# GSM_SIM.net
KiCad netlist of a schematic drawn in Altium Designer
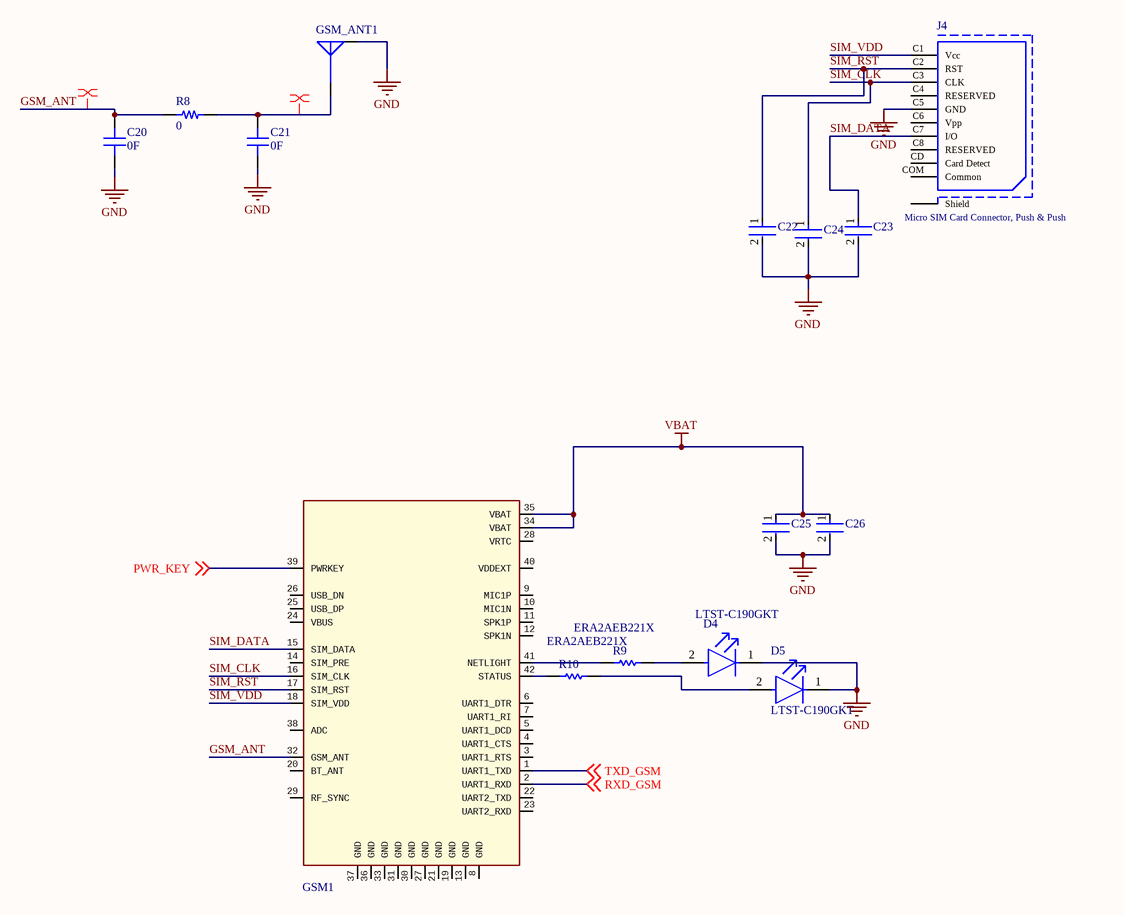
[diagram p0: GSM & SIM.SchDoc]

(export (version "E")
  (design (tool "Eeschema 10.0.6"))
  (components
    (comp (ref "C20")
      (value "0F")
      (footprint "CAP 0402_1005")
      (description "SMT Capacitor")
      (libsource (lib "Capacitor") (part "Cap 0402"))
    )
    (comp (ref "C21")
      (value "0F")
      (footprint "CAP 0402_1005")
      (description "SMT Capacitor")
      (libsource (lib "Capacitor") (part "Cap 0402"))
    )
    (comp (ref "C22")
      (value "04023A330JAT2A")
      (footprint "FP-0402-L_1_0_1-W_0_5_0_1-IPC_A")
      (description "General Purpose Ceramic Capacitor, 0402, 33pF, 5%, C0G, 30ppm/°C, 25V")
      (fields (field (name "TOLERANCE") "5%"))
      (libsource (lib "Altium Content Vault") (part "b4654b650e69147ec39a6b967a45e02"))
    )
    (comp (ref "C23")
      (value "04023A330JAT2A")
      (footprint "FP-0402-L_1_0_1-W_0_5_0_1-IPC_A")
      (description "General Purpose Ceramic Capacitor, 0402, 33pF, 5%, C0G, 30ppm/°C, 25V")
      (fields (field (name "TOLERANCE") "5%"))
      (libsource (lib "Altium Content Vault") (part "b4654b650e69147ec39a6b967a45e02"))
    )
    (comp (ref "C24")
      (value "04023A330JAT2A")
      (footprint "FP-0402-L_1_0_1-W_0_5_0_1-IPC_A")
      (description "General Purpose Ceramic Capacitor, 0402, 33pF, 5%, C0G, 30ppm/°C, 25V")
      (fields (field (name "TOLERANCE") "5%"))
      (libsource (lib "Altium Content Vault") (part "b4654b650e69147ec39a6b967a45e02"))
    )
    (comp (ref "C25")
      (value "04025A330JAT2A")
      (footprint "FP-0402-L_1_0_1-W_0_5_0_1-IPC_A")
      (description "General Purpose Ceramic Capacitor, 0402, 33pF, 5%, C0G, 30ppm/°C, 50V")
      (fields (field (name "TOLERANCE") "5%") (field (name "VOLTAGE") "50V"))
      (libsource (lib "Altium Content Vault") (part "b4654b650e69147ec39a6b967a45e02"))
    )
    (comp (ref "C26")
      (value "C1005C0G1H100D050BA")
      (footprint "FP-C1005-050-0_05-IPC_C")
      (description "CAP CER 10PF 50V C0G 0402")
      (fields (field (name "VOLTAGE") "50V"))
      (libsource (lib "Altium Content Vault") (part "b4654b650e69147ec39a6b967a45e02"))
    )
    (comp (ref "D4")
      (value "LTST-C190GKT")
      (footprint "FP-LTST-C190GKT-MFG")
      (description "LED GREEN CLEAR CHIP SMD")
      (fields (field (name "VOLTAGE") "2V"))
      (libsource (lib "Altium Content Vault") (part "8706943c75ba83719d021d2fdc84c58"))
    )
    (comp (ref "D5")
      (value "LTST-C190GKT")
      (footprint "FP-LTST-C190GKT-MFG")
      (description "LED GREEN CLEAR CHIP SMD")
      (fields (field (name "VOLTAGE") "2V"))
      (libsource (lib "Altium Content Vault") (part "8706943c75ba83719d021d2fdc84c58"))
    )
    (comp (ref "GSM1")
      (value "SIM800C")
      (footprint "Sim800C")
      (libsource (lib "GSM Shutter lock system") (part "SIM800C"))
    )
    (comp (ref "GSM_ANT1")
      (value "UFL")
      (footprint "MOLEX SD-734120110")
      (fields (field (name "PARTNUMBER") "MOLEX SD-734120110"))
      (libsource (lib "Conn RF") (part "UFL MOLEX SD-734120110"))
    )
    (comp (ref "J4")
      (value "Micro SIM Card Connector, Push & Push")
      (footprint "693021010811")
      (description "WR-CRD Micro SIM Card Connector, Push & Push, with Card Detection")
      (fields (field (name "PARTNUMBER") "693021010811") (field (name "PUBLISHER") "Wurth Elektronik"))
      (libsource (lib "Conn Card") (part "Micro SIM Card 693021010811"))
    )
    (comp (ref "R8")
      (value "0")
      (footprint "RES 0402_1005")
      (description "SMT Resistor")
      (libsource (lib "Resistor") (part "Res 0402"))
    )
    (comp (ref "R9")
      (value "ERA2AEB221X")
      (footprint "RESC1005X40X25LL10T10")
      (fields (field (name "MANUFACTURER") "Panasonic"))
      (libsource (lib "Altium Content Vault") (part "RES"))
    )
    (comp (ref "R10")
      (value "ERA2AEB221X")
      (footprint "RESC1005X40X25LL10T10")
      (fields (field (name "MANUFACTURER") "Panasonic"))
      (libsource (lib "Altium Content Vault") (part "RES"))
    )
  )
  (nets
    (net (code "1") (name "/GSM_ANT") (class "Default")
      (node (ref "C20") (pin "2") (pinfunction "2_2") (pintype "passive"))
      (node (ref "GSM1") (pin "32") (pinfunction "GSM_ANT_32") (pintype "passive"))
      (node (ref "R8") (pin "1") (pinfunction "1_1") (pintype "passive"))
    )
    (net (code "2") (name "/SIM_CLK") (class "Default")
      (node (ref "C24") (pin "1") (pinfunction "1_1") (pintype "passive"))
      (node (ref "GSM1") (pin "16") (pinfunction "SIM_CLK_16") (pintype "passive"))
      (node (ref "J4") (pin "C3") (pinfunction "CLK_C3") (pintype "passive"))
    )
    (net (code "3") (name "/SIM_DATA") (class "Default")
      (node (ref "C23") (pin "1") (pinfunction "1_1") (pintype "passive"))
      (node (ref "GSM1") (pin "15") (pinfunction "SIM_DATA_15") (pintype "passive"))
      (node (ref "J4") (pin "C7") (pinfunction "I/O_C7") (pintype "passive"))
    )
    (net (code "4") (name "/SIM_RST") (class "Default")
      (node (ref "C22") (pin "1") (pinfunction "1_1") (pintype "passive"))
      (node (ref "GSM1") (pin "17") (pinfunction "SIM_RST_17") (pintype "passive"))
      (node (ref "J4") (pin "C2") (pinfunction "RST_C2") (pintype "passive"))
    )
    (net (code "5") (name "/SIM_VDD") (class "Default")
      (node (ref "GSM1") (pin "18") (pinfunction "SIM_VDD_18") (pintype "passive"))
      (node (ref "J4") (pin "C1") (pinfunction "Vcc_C1") (pintype "passive"))
    )
    (net (code "6") (name "GND") (class "Default")
      (node (ref "C20") (pin "1") (pinfunction "1_1") (pintype "passive"))
      (node (ref "C21") (pin "1") (pinfunction "1_1") (pintype "passive"))
      (node (ref "C22") (pin "2") (pinfunction "2_2") (pintype "passive"))
      (node (ref "C23") (pin "2") (pinfunction "2_2") (pintype "passive"))
      (node (ref "C24") (pin "2") (pinfunction "2_2") (pintype "passive"))
      (node (ref "C25") (pin "2") (pinfunction "2_2") (pintype "passive"))
      (node (ref "C26") (pin "2") (pinfunction "2_2") (pintype "passive"))
      (node (ref "D4") (pin "1") (pinfunction "C_1") (pintype "passive"))
      (node (ref "D5") (pin "1") (pinfunction "C_1") (pintype "passive"))
      (node (ref "GSM_ANT1") (pin "G") (pinfunction "G_G") (pintype "passive"))
      (node (ref "J4") (pin "C5") (pinfunction "GND_C5") (pintype "passive"))
    )
    (net (code "7") (name "Net-(C21-Pad2)") (class "Default")
      (node (ref "C21") (pin "2") (pinfunction "2_2") (pintype "passive"))
      (node (ref "GSM_ANT1") (pin "S") (pinfunction "S_S") (pintype "passive"))
      (node (ref "R8") (pin "2") (pinfunction "2_2") (pintype "passive"))
    )
    (net (code "8") (name "Net-(D4-A)") (class "Default")
      (node (ref "D4") (pin "2") (pinfunction "A_2") (pintype "passive"))
      (node (ref "R9") (pin "2") (pinfunction "2_2") (pintype "passive"))
    )
    (net (code "9") (name "Net-(D5-A)") (class "Default")
      (node (ref "D5") (pin "2") (pinfunction "A_2") (pintype "passive"))
      (node (ref "R10") (pin "2") (pinfunction "2_2") (pintype "passive"))
    )
    (net (code "10") (name "Net-(GSM1-NETLIGHT)") (class "Default")
      (node (ref "GSM1") (pin "41") (pinfunction "NETLIGHT_41") (pintype "passive"))
      (node (ref "R9") (pin "1") (pinfunction "1_1") (pintype "passive"))
    )
    (net (code "11") (name "Net-(GSM1-STATUS)") (class "Default")
      (node (ref "GSM1") (pin "42") (pinfunction "STATUS_42") (pintype "passive"))
      (node (ref "R10") (pin "1") (pinfunction "1_1") (pintype "passive"))
    )
    (net (code "12") (name "PWR_KEY") (class "Default")
      (node (ref "GSM1") (pin "39") (pinfunction "PWRKEY_39") (pintype "passive"))
    )
    (net (code "13") (name "RXD_GSM") (class "Default")
      (node (ref "GSM1") (pin "2") (pinfunction "UART1_RXD_2") (pintype "passive"))
    )
    (net (code "14") (name "TXD_GSM") (class "Default")
      (node (ref "GSM1") (pin "1") (pinfunction "UART1_TXD_1") (pintype "passive"))
    )
    (net (code "15") (name "VBAT") (class "Default")
      (node (ref "C25") (pin "1") (pinfunction "1_1") (pintype "passive"))
      (node (ref "C26") (pin "1") (pinfunction "1_1") (pintype "passive"))
      (node (ref "GSM1") (pin "34") (pinfunction "VBAT_34") (pintype "passive"))
      (node (ref "GSM1") (pin "35") (pinfunction "VBAT_35") (pintype "passive"))
    )
    (net (code "16") (name "unconnected-(GSM1-ADC-Pad38)") (class "Default")
      (node (ref "GSM1") (pin "38") (pinfunction "ADC_38") (pintype "passive"))
    )
    (net (code "17") (name "unconnected-(GSM1-BT_ANT-Pad20)") (class "Default")
      (node (ref "GSM1") (pin "20") (pinfunction "BT_ANT_20") (pintype "passive"))
    )
    (net (code "18") (name "unconnected-(GSM1-GND-Pad8)") (class "Default")
      (node (ref "GSM1") (pin "8") (pinfunction "GND_8") (pintype "passive"))
    )
    (net (code "19") (name "unconnected-(GSM1-GND-Pad13)") (class "Default")
      (node (ref "GSM1") (pin "13") (pinfunction "GND_13") (pintype "passive"))
    )
    (net (code "20") (name "unconnected-(GSM1-GND-Pad19)") (class "Default")
      (node (ref "GSM1") (pin "19") (pinfunction "GND_19") (pintype "passive"))
    )
    (net (code "21") (name "unconnected-(GSM1-GND-Pad21)") (class "Default")
      (node (ref "GSM1") (pin "21") (pinfunction "GND_21") (pintype "passive"))
    )
    (net (code "22") (name "unconnected-(GSM1-GND-Pad27)") (class "Default")
      (node (ref "GSM1") (pin "27") (pinfunction "GND_27") (pintype "passive"))
    )
    (net (code "23") (name "unconnected-(GSM1-GND-Pad30)") (class "Default")
      (node (ref "GSM1") (pin "30") (pinfunction "GND_30") (pintype "passive"))
    )
    (net (code "24") (name "unconnected-(GSM1-GND-Pad31)") (class "Default")
      (node (ref "GSM1") (pin "31") (pinfunction "GND_31") (pintype "passive"))
    )
    (net (code "25") (name "unconnected-(GSM1-GND-Pad33)") (class "Default")
      (node (ref "GSM1") (pin "33") (pinfunction "GND_33") (pintype "passive"))
    )
    (net (code "26") (name "unconnected-(GSM1-GND-Pad36)") (class "Default")
      (node (ref "GSM1") (pin "36") (pinfunction "GND_36") (pintype "passive"))
    )
    (net (code "27") (name "unconnected-(GSM1-GND-Pad37)") (class "Default")
      (node (ref "GSM1") (pin "37") (pinfunction "GND_37") (pintype "passive"))
    )
    (net (code "28") (name "unconnected-(GSM1-MIC1N-Pad10)") (class "Default")
      (node (ref "GSM1") (pin "10") (pinfunction "MIC1N_10") (pintype "passive"))
    )
    (net (code "29") (name "unconnected-(GSM1-MIC1P-Pad9)") (class "Default")
      (node (ref "GSM1") (pin "9") (pinfunction "MIC1P_9") (pintype "passive"))
    )
    (net (code "30") (name "unconnected-(GSM1-RF_SYNC-Pad29)") (class "Default")
      (node (ref "GSM1") (pin "29") (pinfunction "RF_SYNC_29") (pintype "passive"))
    )
    (net (code "31") (name "unconnected-(GSM1-SIM_PRE-Pad14)") (class "Default")
      (node (ref "GSM1") (pin "14") (pinfunction "SIM_PRE_14") (pintype "passive"))
    )
    (net (code "32") (name "unconnected-(GSM1-SPK1N-Pad12)") (class "Default")
      (node (ref "GSM1") (pin "12") (pinfunction "SPK1N_12") (pintype "passive"))
    )
    (net (code "33") (name "unconnected-(GSM1-SPK1P-Pad11)") (class "Default")
      (node (ref "GSM1") (pin "11") (pinfunction "SPK1P_11") (pintype "passive"))
    )
    (net (code "34") (name "unconnected-(GSM1-UART1_CTS-Pad4)") (class "Default")
      (node (ref "GSM1") (pin "4") (pinfunction "UART1_CTS_4") (pintype "passive"))
    )
    (net (code "35") (name "unconnected-(GSM1-UART1_DCD-Pad5)") (class "Default")
      (node (ref "GSM1") (pin "5") (pinfunction "UART1_DCD_5") (pintype "passive"))
    )
    (net (code "36") (name "unconnected-(GSM1-UART1_DTR-Pad6)") (class "Default")
      (node (ref "GSM1") (pin "6") (pinfunction "UART1_DTR_6") (pintype "passive"))
    )
    (net (code "37") (name "unconnected-(GSM1-UART1_RI-Pad7)") (class "Default")
      (node (ref "GSM1") (pin "7") (pinfunction "UART1_RI_7") (pintype "passive"))
    )
    (net (code "38") (name "unconnected-(GSM1-UART1_RTS-Pad3)") (class "Default")
      (node (ref "GSM1") (pin "3") (pinfunction "UART1_RTS_3") (pintype "passive"))
    )
    (net (code "39") (name "unconnected-(GSM1-UART2_RXD-Pad23)") (class "Default")
      (node (ref "GSM1") (pin "23") (pinfunction "UART2_RXD_23") (pintype "passive"))
    )
    (net (code "40") (name "unconnected-(GSM1-UART2_TXD-Pad22)") (class "Default")
      (node (ref "GSM1") (pin "22") (pinfunction "UART2_TXD_22") (pintype "passive"))
    )
    (net (code "41") (name "unconnected-(GSM1-USB_DN-Pad26)") (class "Default")
      (node (ref "GSM1") (pin "26") (pinfunction "USB_DN_26") (pintype "passive"))
    )
    (net (code "42") (name "unconnected-(GSM1-USB_DP-Pad25)") (class "Default")
      (node (ref "GSM1") (pin "25") (pinfunction "USB_DP_25") (pintype "passive"))
    )
    (net (code "43") (name "unconnected-(GSM1-VBUS-Pad24)") (class "Default")
      (node (ref "GSM1") (pin "24") (pinfunction "VBUS_24") (pintype "passive"))
    )
    (net (code "44") (name "unconnected-(GSM1-VDDEXT-Pad40)") (class "Default")
      (node (ref "GSM1") (pin "40") (pinfunction "VDDEXT_40") (pintype "passive"))
    )
    (net (code "45") (name "unconnected-(GSM1-VRTC-Pad28)") (class "Default")
      (node (ref "GSM1") (pin "28") (pinfunction "VRTC_28") (pintype "passive"))
    )
    (net (code "46") (name "unconnected-(J4-Card_Detect-PadCD)") (class "Default")
      (node (ref "J4") (pin "CD") (pinfunction "Card_Detect_CD") (pintype "passive"))
    )
    (net (code "47") (name "unconnected-(J4-Common-PadCOM)") (class "Default")
      (node (ref "J4") (pin "COM") (pinfunction "Common_COM") (pintype "passive"))
    )
    (net (code "48") (name "unconnected-(J4-PadShield)") (class "Default")
      (node (ref "J4") (pin "Shield") (pinfunction "Shield_Shield") (pintype "passive"))
    )
    (net (code "49") (name "unconnected-(J4-RESERVED-PadC4)") (class "Default")
      (node (ref "J4") (pin "C4") (pinfunction "RESERVED_C4") (pintype "passive"))
    )
    (net (code "50") (name "unconnected-(J4-RESERVED-PadC8)") (class "Default")
      (node (ref "J4") (pin "C8") (pinfunction "RESERVED_C8") (pintype "passive"))
    )
    (net (code "51") (name "unconnected-(J4-Vpp-PadC6)") (class "Default")
      (node (ref "J4") (pin "C6") (pinfunction "Vpp_C6") (pintype "passive"))
    )
  )
)
